# MotorTest.net
KiCad netlist of a schematic drawn in Altium Designer
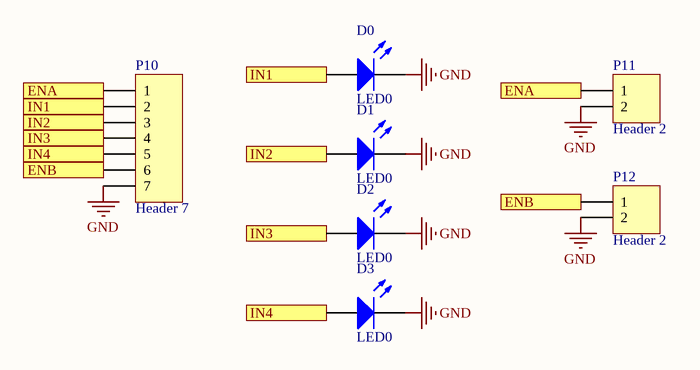
[diagram p0: MotorTest.SchDoc]

(export (version "E")
  (design (tool "Eeschema 10.0.6"))
  (components
    (comp (ref "D0")
      (value "LED0")
      (footprint "LED-0")
      (description "Typical INFRARED GaAs LED")
      (fields (field (name "PUBLISHER") "Altium Limited"))
      (libsource (lib "Miscellaneous Devices") (part "LED0"))
    )
    (comp (ref "D1")
      (value "LED0")
      (footprint "LED-0")
      (description "Typical INFRARED GaAs LED")
      (fields (field (name "PUBLISHER") "Altium Limited"))
      (libsource (lib "Miscellaneous Devices") (part "LED0"))
    )
    (comp (ref "D2")
      (value "LED0")
      (footprint "LED-0")
      (description "Typical INFRARED GaAs LED")
      (fields (field (name "PUBLISHER") "Altium Limited"))
      (libsource (lib "Miscellaneous Devices") (part "LED0"))
    )
    (comp (ref "D3")
      (value "LED0")
      (footprint "LED-0")
      (description "Typical INFRARED GaAs LED")
      (fields (field (name "PUBLISHER") "Altium Limited"))
      (libsource (lib "Miscellaneous Devices") (part "LED0"))
    )
    (comp (ref "P10")
      (value "Header 7")
      (footprint "HDR1X7")
      (description "Header, 7-Pin")
      (fields (field (name "PUBLISHER") "Altium Limited"))
      (libsource (lib "Miscellaneous Connectors") (part "Header 7"))
    )
    (comp (ref "P11")
      (value "Header 2")
      (footprint "HDR1X2")
      (description "Header, 2-Pin")
      (fields (field (name "PUBLISHER") "Altium Limited"))
      (libsource (lib "Miscellaneous Connectors") (part "Header 2"))
    )
    (comp (ref "P12")
      (value "Header 2")
      (footprint "HDR1X2")
      (description "Header, 2-Pin")
      (fields (field (name "PUBLISHER") "Altium Limited"))
      (libsource (lib "Miscellaneous Connectors") (part "Header 2"))
    )
  )
  (nets
    (net (code "1") (name "/ENA") (class "Default")
      (node (ref "P10") (pin "1") (pinfunction "1_1") (pintype "passive"))
      (node (ref "P11") (pin "1") (pinfunction "1_1") (pintype "passive"))
    )
    (net (code "2") (name "/ENB") (class "Default")
      (node (ref "P10") (pin "6") (pinfunction "6_6") (pintype "passive"))
      (node (ref "P12") (pin "1") (pinfunction "1_1") (pintype "passive"))
    )
    (net (code "3") (name "/IN1") (class "Default")
      (node (ref "D0") (pin "1") (pinfunction "A_1") (pintype "passive"))
      (node (ref "P10") (pin "2") (pinfunction "2_2") (pintype "passive"))
    )
    (net (code "4") (name "/IN2") (class "Default")
      (node (ref "D1") (pin "1") (pinfunction "A_1") (pintype "passive"))
      (node (ref "P10") (pin "3") (pinfunction "3_3") (pintype "passive"))
    )
    (net (code "5") (name "/IN3") (class "Default")
      (node (ref "D2") (pin "1") (pinfunction "A_1") (pintype "passive"))
      (node (ref "P10") (pin "4") (pinfunction "4_4") (pintype "passive"))
    )
    (net (code "6") (name "/IN4") (class "Default")
      (node (ref "D3") (pin "1") (pinfunction "A_1") (pintype "passive"))
      (node (ref "P10") (pin "5") (pinfunction "5_5") (pintype "passive"))
    )
    (net (code "7") (name "GND") (class "Default")
      (node (ref "D0") (pin "2") (pinfunction "K_2") (pintype "passive"))
      (node (ref "D1") (pin "2") (pinfunction "K_2") (pintype "passive"))
      (node (ref "D2") (pin "2") (pinfunction "K_2") (pintype "passive"))
      (node (ref "D3") (pin "2") (pinfunction "K_2") (pintype "passive"))
      (node (ref "P10") (pin "7") (pinfunction "7_7") (pintype "passive"))
      (node (ref "P11") (pin "2") (pinfunction "2_2") (pintype "passive"))
      (node (ref "P12") (pin "2") (pinfunction "2_2") (pintype "passive"))
    )
  )
)
